# SAM3U_Test_Schematic.net
KiCad netlist of a schematic drawn in EAGLE
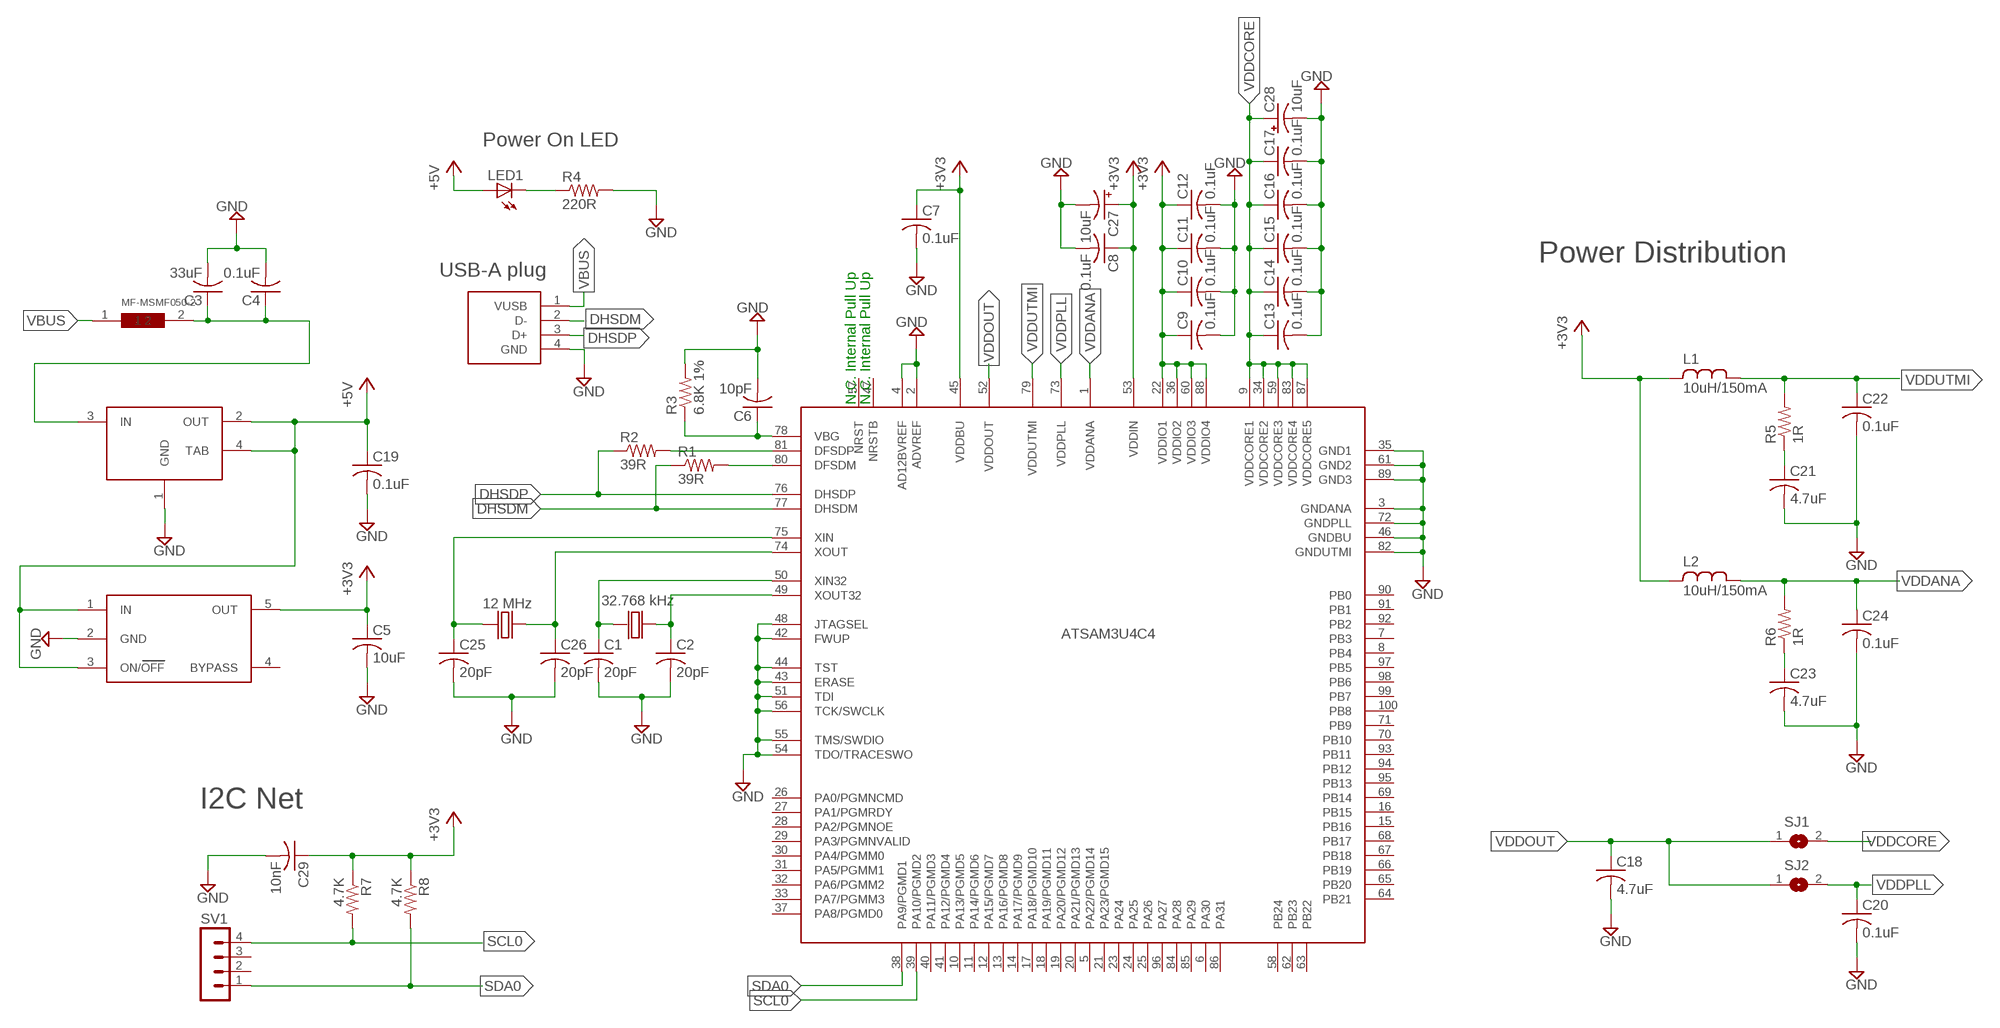
[diagram p0: schematic, sheet 1]

(export (version "E")
  (design (tool "Eeschema 10.0.6"))
  (components
    (comp (ref "C1")
      (value "20pF")
      (footprint "eagle-import:C0402K")
      (libsource (lib "eagle-import") (part "C-USC0402K"))
    )
    (comp (ref "C2")
      (value "20pF")
      (footprint "eagle-import:C0402K")
      (libsource (lib "eagle-import") (part "C-USC0402K"))
    )
    (comp (ref "C3")
      (value "33uF")
      (footprint "eagle-import:C0805K")
      (libsource (lib "eagle-import") (part "C-USC0805K"))
    )
    (comp (ref "C4")
      (value "0.1uF")
      (footprint "eagle-import:C0402K")
      (libsource (lib "eagle-import") (part "C-USC0402K"))
    )
    (comp (ref "C5")
      (value "10uF")
      (footprint "eagle-import:C0402K")
      (libsource (lib "eagle-import") (part "C-USC0402K"))
    )
    (comp (ref "C6")
      (value "10pF")
      (footprint "eagle-import:C0402K")
      (libsource (lib "eagle-import") (part "C-USC0402K"))
    )
    (comp (ref "C7")
      (value "0.1uF")
      (footprint "eagle-import:C0402K")
      (libsource (lib "eagle-import") (part "C-USC0402K"))
    )
    (comp (ref "C8")
      (value "0.1uF")
      (footprint "eagle-import:C0402K")
      (libsource (lib "eagle-import") (part "C-USC0402K"))
    )
    (comp (ref "C9")
      (value "0.1uF")
      (footprint "eagle-import:C0402K")
      (libsource (lib "eagle-import") (part "C-USC0402K"))
    )
    (comp (ref "C10")
      (value "0.1uF")
      (footprint "eagle-import:C0402K")
      (libsource (lib "eagle-import") (part "C-USC0402K"))
    )
    (comp (ref "C11")
      (value "0.1uF")
      (footprint "eagle-import:C0402K")
      (libsource (lib "eagle-import") (part "C-USC0402K"))
    )
    (comp (ref "C12")
      (value "0.1uF")
      (footprint "eagle-import:C0402K")
      (libsource (lib "eagle-import") (part "C-USC0402K"))
    )
    (comp (ref "C13")
      (value "0.1uF")
      (footprint "eagle-import:C0402K")
      (libsource (lib "eagle-import") (part "C-USC0402K"))
    )
    (comp (ref "C14")
      (value "0.1uF")
      (footprint "eagle-import:C0402K")
      (libsource (lib "eagle-import") (part "C-USC0402K"))
    )
    (comp (ref "C15")
      (value "0.1uF")
      (footprint "eagle-import:C0402K")
      (libsource (lib "eagle-import") (part "C-USC0402K"))
    )
    (comp (ref "C16")
      (value "0.1uF")
      (footprint "eagle-import:C0402K")
      (libsource (lib "eagle-import") (part "C-USC0402K"))
    )
    (comp (ref "C17")
      (value "0.1uF")
      (footprint "eagle-import:C0402K")
      (libsource (lib "eagle-import") (part "C-USC0402K"))
    )
    (comp (ref "C18")
      (value "4.7uF")
      (footprint "eagle-import:C0402K")
      (libsource (lib "eagle-import") (part "C-USC0402K"))
    )
    (comp (ref "C19")
      (value "0.1uF")
      (footprint "eagle-import:C0402K")
      (libsource (lib "eagle-import") (part "C-USC0402K"))
    )
    (comp (ref "C20")
      (value "0.1uF")
      (footprint "eagle-import:C0402K")
      (libsource (lib "eagle-import") (part "C-USC0402K"))
    )
    (comp (ref "C21")
      (value "4.7uF")
      (footprint "eagle-import:C0402K")
      (libsource (lib "eagle-import") (part "C-USC0402K"))
    )
    (comp (ref "C22")
      (value "0.1uF")
      (footprint "eagle-import:C0402K")
      (libsource (lib "eagle-import") (part "C-USC0402K"))
    )
    (comp (ref "C23")
      (value "4.7uF")
      (footprint "eagle-import:C0402K")
      (libsource (lib "eagle-import") (part "C-USC0402K"))
    )
    (comp (ref "C24")
      (value "0.1uF")
      (footprint "eagle-import:C0402K")
      (libsource (lib "eagle-import") (part "C-USC0402K"))
    )
    (comp (ref "C25")
      (value "20pF")
      (footprint "eagle-import:C0402K")
      (libsource (lib "eagle-import") (part "C-USC0402K"))
    )
    (comp (ref "C26")
      (value "20pF")
      (footprint "eagle-import:C0402K")
      (libsource (lib "eagle-import") (part "C-USC0402K"))
    )
    (comp (ref "C27")
      (value "10uF")
      (footprint "eagle-import:A_3216-18R")
      (libsource (lib "eagle-import") (part "CPOL-USA/3216-18R"))
    )
    (comp (ref "C28")
      (value "10uF")
      (footprint "eagle-import:A_3216-18R")
      (libsource (lib "eagle-import") (part "CPOL-USA/3216-18R"))
    )
    (comp (ref "C29")
      (value "10nF")
      (footprint "eagle-import:C0402K")
      (libsource (lib "eagle-import") (part "C-USC0402K"))
    )
    (comp (ref "L1")
      (value "TDK_MLZ2012_INDUCTOR")
      (footprint "eagle-import:TDK_MLZ_INDUCTOR_2012PACK")
      (libsource (lib "eagle-import") (part "TDK_MLZ2012_INDUCTOR"))
    )
    (comp (ref "L2")
      (value "TDK_MLZ2012_INDUCTOR")
      (footprint "eagle-import:TDK_MLZ_INDUCTOR_2012PACK")
      (libsource (lib "eagle-import") (part "TDK_MLZ2012_INDUCTOR"))
    )
    (comp (ref "LED1")
      (value "LEDCHIPLED_0603")
      (footprint "eagle-import:CHIPLED_0603")
      (libsource (lib "eagle-import") (part "LEDCHIPLED_0603"))
    )
    (comp (ref "R1")
      (value "39R")
      (footprint "eagle-import:R0402")
      (libsource (lib "eagle-import") (part "R-US_R0402"))
    )
    (comp (ref "R2")
      (value "39R")
      (footprint "eagle-import:R0402")
      (libsource (lib "eagle-import") (part "R-US_R0402"))
    )
    (comp (ref "R3")
      (value "6.8K 1%")
      (footprint "eagle-import:R0402")
      (libsource (lib "eagle-import") (part "R-US_R0402"))
    )
    (comp (ref "R4")
      (value "220R")
      (footprint "eagle-import:R0402")
      (libsource (lib "eagle-import") (part "R-US_R0402"))
    )
    (comp (ref "R5")
      (value "1R")
      (footprint "eagle-import:R0402")
      (libsource (lib "eagle-import") (part "R-US_R0402"))
    )
    (comp (ref "R6")
      (value "1R")
      (footprint "eagle-import:R0402")
      (libsource (lib "eagle-import") (part "R-US_R0402"))
    )
    (comp (ref "R7")
      (value "4.7K")
      (footprint "eagle-import:R0402")
      (libsource (lib "eagle-import") (part "R-US_R0402"))
    )
    (comp (ref "R8")
      (value "4.7K")
      (footprint "eagle-import:R0402")
      (libsource (lib "eagle-import") (part "R-US_R0402"))
    )
    (comp (ref "SJ1") (value "SJ") (footprint "eagle-import:SJ") (libsource (lib "eagle-import") (part "SJ")))
    (comp (ref "SJ2") (value "SJ") (footprint "eagle-import:SJ") (libsource (lib "eagle-import") (part "SJ")))
    (comp (ref "SV1")
      (value "MA04-1")
      (footprint "eagle-import:MA04-1")
      (libsource (lib "eagle-import") (part "MA04-1"))
    )
    (comp (ref "U$1")
      (value "USB_TYPE_A_KEYSTN")
      (footprint "eagle-import:USB_TYPE_PLUG_KSTN_PACK")
      (libsource (lib "eagle-import") (part "USB_TYPE_A_KEYSTN"))
    )
    (comp (ref "U$2")
      (value "ATSAM3UC4-PA")
      (footprint "eagle-import:QFP50P1600X1600X160-100N")
      (libsource (lib "eagle-import") (part "ATSAM3UC4-PA"))
    )
    (comp (ref "U$3")
      (value "32678_KYOCERA")
      (footprint "eagle-import:32678_KYOCERA_PACK")
      (libsource (lib "eagle-import") (part "32678_KYOCERA"))
    )
    (comp (ref "U$4")
      (value "MF-MSMF050-2")
      (footprint "eagle-import:MF-MSMF050-PACK")
      (libsource (lib "eagle-import") (part "MF-MSMF050-2"))
    )
    (comp (ref "U$5")
      (value "NCP1117-55V")
      (footprint "eagle-import:NCP1117-5-SOT")
      (libsource (lib "eagle-import") (part "NCP1117-55V"))
    )
    (comp (ref "U$6")
      (value "LP2985-33DBVR5-PIN")
      (footprint "eagle-import:LP2985-33DBVR-SO")
      (libsource (lib "eagle-import") (part "LP2985-33DBVR5-PIN"))
    )
    (comp (ref "U$7")
      (value "AVX_12MHZ_CRYSTAL_CX3225GB")
      (footprint "eagle-import:AVX_12MHZ_CX3225GB_PACK")
      (libsource (lib "eagle-import") (part "AVX_12MHZ_CRYSTAL_CX3225GB"))
    )
  )
  (nets
    (net (code "1") (name "+3V3") (class "Default")
      (node (ref "C10") (pin "1") (pinfunction "1_1") (pintype "passive"))
      (node (ref "C11") (pin "1") (pinfunction "1_1") (pintype "passive"))
      (node (ref "C12") (pin "1") (pinfunction "1_1") (pintype "passive"))
      (node (ref "C27") (pin "+") (pinfunction "+_+") (pintype "passive"))
      (node (ref "C29") (pin "1") (pinfunction "1_1") (pintype "passive"))
      (node (ref "C5") (pin "1") (pinfunction "1_1") (pintype "passive"))
      (node (ref "C7") (pin "1") (pinfunction "1_1") (pintype "passive"))
      (node (ref "C8") (pin "1") (pinfunction "1_1") (pintype "passive"))
      (node (ref "C9") (pin "1") (pinfunction "1_1") (pintype "passive"))
      (node (ref "L1") (pin "1") (pinfunction "P$1_1") (pintype "bidirectional"))
      (node (ref "L2") (pin "1") (pinfunction "P$1_1") (pintype "bidirectional"))
      (node (ref "R7") (pin "1") (pinfunction "1_1") (pintype "passive"))
      (node (ref "R8") (pin "1") (pinfunction "1_1") (pintype "passive"))
      (node (ref "U$2") (pin "22") (pinfunction "VDDIO1_22") (pintype "bidirectional"))
      (node (ref "U$2") (pin "36") (pinfunction "VDDIO2_36") (pintype "bidirectional"))
      (node (ref "U$2") (pin "45") (pinfunction "VDDBU_45") (pintype "bidirectional"))
      (node (ref "U$2") (pin "53") (pinfunction "VDDIN_53") (pintype "bidirectional"))
      (node (ref "U$2") (pin "60") (pinfunction "VDDIO3_60") (pintype "bidirectional"))
      (node (ref "U$2") (pin "88") (pinfunction "VDDIO4_88") (pintype "bidirectional"))
      (node (ref "U$6") (pin "5") (pinfunction "OUT_5") (pintype "bidirectional"))
    )
    (net (code "2") (name "+5V") (class "Default")
      (node (ref "C19") (pin "1") (pinfunction "1_1") (pintype "passive"))
      (node (ref "LED1") (pin "A") (pinfunction "A_A") (pintype "passive"))
      (node (ref "U$5") (pin "2") (pinfunction "OUT_2") (pintype "bidirectional"))
      (node (ref "U$5") (pin "4") (pinfunction "TAB_4") (pintype "bidirectional"))
      (node (ref "U$6") (pin "1") (pinfunction "IN_1") (pintype "bidirectional"))
      (node (ref "U$6") (pin "3") (pinfunction "ON/OFF_3") (pintype "bidirectional"))
    )
    (net (code "3") (name "DHSDM") (class "Default")
      (node (ref "R1") (pin "1") (pinfunction "1_1") (pintype "passive"))
      (node (ref "U$1") (pin "2") (pinfunction "D-_2") (pintype "bidirectional"))
      (node (ref "U$2") (pin "77") (pinfunction "DHSDM_77") (pintype "bidirectional"))
    )
    (net (code "4") (name "DHSDP") (class "Default")
      (node (ref "R2") (pin "1") (pinfunction "1_1") (pintype "passive"))
      (node (ref "U$1") (pin "3") (pinfunction "D+_3") (pintype "bidirectional"))
      (node (ref "U$2") (pin "76") (pinfunction "DHSDP_76") (pintype "bidirectional"))
    )
    (net (code "5") (name "GND") (class "Default")
      (node (ref "C1") (pin "2") (pinfunction "2_2") (pintype "passive"))
      (node (ref "C10") (pin "2") (pinfunction "2_2") (pintype "passive"))
      (node (ref "C11") (pin "2") (pinfunction "2_2") (pintype "passive"))
      (node (ref "C12") (pin "2") (pinfunction "2_2") (pintype "passive"))
      (node (ref "C13") (pin "2") (pinfunction "2_2") (pintype "passive"))
      (node (ref "C14") (pin "2") (pinfunction "2_2") (pintype "passive"))
      (node (ref "C15") (pin "2") (pinfunction "2_2") (pintype "passive"))
      (node (ref "C16") (pin "2") (pinfunction "2_2") (pintype "passive"))
      (node (ref "C17") (pin "2") (pinfunction "2_2") (pintype "passive"))
      (node (ref "C18") (pin "2") (pinfunction "2_2") (pintype "passive"))
      (node (ref "C19") (pin "2") (pinfunction "2_2") (pintype "passive"))
      (node (ref "C2") (pin "2") (pinfunction "2_2") (pintype "passive"))
      (node (ref "C20") (pin "2") (pinfunction "2_2") (pintype "passive"))
      (node (ref "C21") (pin "2") (pinfunction "2_2") (pintype "passive"))
      (node (ref "C22") (pin "2") (pinfunction "2_2") (pintype "passive"))
      (node (ref "C23") (pin "2") (pinfunction "2_2") (pintype "passive"))
      (node (ref "C24") (pin "2") (pinfunction "2_2") (pintype "passive"))
      (node (ref "C25") (pin "2") (pinfunction "2_2") (pintype "passive"))
      (node (ref "C26") (pin "2") (pinfunction "2_2") (pintype "passive"))
      (node (ref "C27") (pin "-") (pinfunction "-_-") (pintype "passive"))
      (node (ref "C28") (pin "-") (pinfunction "-_-") (pintype "passive"))
      (node (ref "C29") (pin "2") (pinfunction "2_2") (pintype "passive"))
      (node (ref "C3") (pin "2") (pinfunction "2_2") (pintype "passive"))
      (node (ref "C4") (pin "2") (pinfunction "2_2") (pintype "passive"))
      (node (ref "C5") (pin "2") (pinfunction "2_2") (pintype "passive"))
      (node (ref "C6") (pin "2") (pinfunction "2_2") (pintype "passive"))
      (node (ref "C7") (pin "2") (pinfunction "2_2") (pintype "passive"))
      (node (ref "C8") (pin "2") (pinfunction "2_2") (pintype "passive"))
      (node (ref "C9") (pin "2") (pinfunction "2_2") (pintype "passive"))
      (node (ref "R3") (pin "2") (pinfunction "2_2") (pintype "passive"))
      (node (ref "R4") (pin "2") (pinfunction "2_2") (pintype "passive"))
      (node (ref "U$1") (pin "4") (pinfunction "GND_4") (pintype "bidirectional"))
      (node (ref "U$2") (pin "2") (pinfunction "ADVREF_2") (pintype "bidirectional"))
      (node (ref "U$2") (pin "3") (pinfunction "GNDANA_3") (pintype "bidirectional"))
      (node (ref "U$2") (pin "35") (pinfunction "GND1_35") (pintype "bidirectional"))
      (node (ref "U$2") (pin "4") (pinfunction "AD12BVREF_4") (pintype "bidirectional"))
      (node (ref "U$2") (pin "42") (pinfunction "FWUP_42") (pintype "bidirectional"))
      (node (ref "U$2") (pin "43") (pinfunction "ERASE_43") (pintype "bidirectional"))
      (node (ref "U$2") (pin "44") (pinfunction "TST_44") (pintype "bidirectional"))
      (node (ref "U$2") (pin "46") (pinfunction "GNDBU_46") (pintype "bidirectional"))
      (node (ref "U$2") (pin "48") (pinfunction "JTAGSEL_48") (pintype "bidirectional"))
      (node (ref "U$2") (pin "51") (pinfunction "TDI_51") (pintype "bidirectional"))
      (node (ref "U$2") (pin "54") (pinfunction "TDO/TRACESWO_54") (pintype "bidirectional"))
      (node (ref "U$2") (pin "55") (pinfunction "TMS/SWDIO_55") (pintype "bidirectional"))
      (node (ref "U$2") (pin "56") (pinfunction "TCK/SWCLK_56") (pintype "bidirectional"))
      (node (ref "U$2") (pin "61") (pinfunction "GND2_61") (pintype "bidirectional"))
      (node (ref "U$2") (pin "72") (pinfunction "GNDPLL_72") (pintype "bidirectional"))
      (node (ref "U$2") (pin "82") (pinfunction "GNDUTMI_82") (pintype "bidirectional"))
      (node (ref "U$2") (pin "89") (pinfunction "GND3_89") (pintype "bidirectional"))
      (node (ref "U$5") (pin "1") (pinfunction "GND_1") (pintype "bidirectional"))
      (node (ref "U$6") (pin "2") (pinfunction "GND_2") (pintype "bidirectional"))
    )
    (net (code "6") (name "Net-(C21-Pad1)") (class "Default")
      (node (ref "C21") (pin "1") (pinfunction "1_1") (pintype "passive"))
      (node (ref "R5") (pin "1") (pinfunction "1_1") (pintype "passive"))
    )
    (net (code "7") (name "Net-(C23-Pad1)") (class "Default")
      (node (ref "C23") (pin "1") (pinfunction "1_1") (pintype "passive"))
      (node (ref "R6") (pin "1") (pinfunction "1_1") (pintype "passive"))
    )
    (net (code "8") (name "Net-(LED1-PadC)") (class "Default")
      (node (ref "LED1") (pin "C") (pinfunction "C_C") (pintype "passive"))
      (node (ref "R4") (pin "1") (pinfunction "1_1") (pintype "passive"))
    )
    (net (code "9") (name "Net-(U$2-DFSDM)") (class "Default")
      (node (ref "R1") (pin "2") (pinfunction "2_2") (pintype "passive"))
      (node (ref "U$2") (pin "80") (pinfunction "DFSDM_80") (pintype "bidirectional"))
    )
    (net (code "10") (name "Net-(U$2-DFSDP)") (class "Default")
      (node (ref "R2") (pin "2") (pinfunction "2_2") (pintype "passive"))
      (node (ref "U$2") (pin "81") (pinfunction "DFSDP_81") (pintype "bidirectional"))
    )
    (net (code "11") (name "Net-(U$2-VBG)") (class "Default")
      (node (ref "C6") (pin "1") (pinfunction "1_1") (pintype "passive"))
      (node (ref "R3") (pin "1") (pinfunction "1_1") (pintype "passive"))
      (node (ref "U$2") (pin "78") (pinfunction "VBG_78") (pintype "bidirectional"))
    )
    (net (code "12") (name "Net-(U$2-XIN)") (class "Default")
      (node (ref "C25") (pin "1") (pinfunction "1_1") (pintype "passive"))
      (node (ref "U$2") (pin "75") (pinfunction "XIN_75") (pintype "bidirectional"))
      (node (ref "U$7") (pin "1") (pinfunction "P$1_1") (pintype "bidirectional"))
    )
    (net (code "13") (name "Net-(U$2-XIN32)") (class "Default")
      (node (ref "C1") (pin "1") (pinfunction "1_1") (pintype "passive"))
      (node (ref "U$2") (pin "50") (pinfunction "XIN32_50") (pintype "bidirectional"))
      (node (ref "U$3") (pin "1") (pinfunction "P$1_1") (pintype "bidirectional"))
    )
    (net (code "14") (name "Net-(U$2-XOUT)") (class "Default")
      (node (ref "C26") (pin "1") (pinfunction "1_1") (pintype "passive"))
      (node (ref "U$2") (pin "74") (pinfunction "XOUT_74") (pintype "bidirectional"))
      (node (ref "U$7") (pin "3") (pinfunction "P$2_3") (pintype "bidirectional"))
    )
    (net (code "15") (name "Net-(U$2-XOUT32)") (class "Default")
      (node (ref "C2") (pin "1") (pinfunction "1_1") (pintype "passive"))
      (node (ref "U$2") (pin "49") (pinfunction "XOUT32_49") (pintype "bidirectional"))
      (node (ref "U$3") (pin "2") (pinfunction "P$2_2") (pintype "bidirectional"))
    )
    (net (code "16") (name "Net-(U$5-IN)") (class "Default")
      (node (ref "C3") (pin "1") (pinfunction "1_1") (pintype "passive"))
      (node (ref "C4") (pin "1") (pinfunction "1_1") (pintype "passive"))
      (node (ref "U$4") (pin "2") (pinfunction "2_2") (pintype "bidirectional"))
      (node (ref "U$5") (pin "3") (pinfunction "IN_3") (pintype "bidirectional"))
    )
    (net (code "17") (name "SCL0") (class "Default")
      (node (ref "R7") (pin "2") (pinfunction "2_2") (pintype "passive"))
      (node (ref "SV1") (pin "4") (pinfunction "4_4") (pintype "passive"))
      (node (ref "U$2") (pin "39") (pinfunction "PA10/PGMD2_39") (pintype "bidirectional"))
    )
    (net (code "18") (name "SDA0") (class "Default")
      (node (ref "R8") (pin "2") (pinfunction "2_2") (pintype "passive"))
      (node (ref "SV1") (pin "1") (pinfunction "1_1") (pintype "passive"))
      (node (ref "U$2") (pin "38") (pinfunction "PA9/PGMD1_38") (pintype "bidirectional"))
    )
    (net (code "19") (name "VBUS") (class "Default")
      (node (ref "U$1") (pin "1") (pinfunction "VUSB_1") (pintype "bidirectional"))
      (node (ref "U$4") (pin "1") (pinfunction "1_1") (pintype "bidirectional"))
    )
    (net (code "20") (name "VDDANA") (class "Default")
      (node (ref "C24") (pin "1") (pinfunction "1_1") (pintype "passive"))
      (node (ref "L2") (pin "2") (pinfunction "P$2_2") (pintype "bidirectional"))
      (node (ref "R6") (pin "2") (pinfunction "2_2") (pintype "passive"))
      (node (ref "U$2") (pin "1") (pinfunction "VDDANA_1") (pintype "bidirectional"))
    )
    (net (code "21") (name "VDDCORE") (class "Default")
      (node (ref "C13") (pin "1") (pinfunction "1_1") (pintype "passive"))
      (node (ref "C14") (pin "1") (pinfunction "1_1") (pintype "passive"))
      (node (ref "C15") (pin "1") (pinfunction "1_1") (pintype "passive"))
      (node (ref "C16") (pin "1") (pinfunction "1_1") (pintype "passive"))
      (node (ref "C17") (pin "1") (pinfunction "1_1") (pintype "passive"))
      (node (ref "C28") (pin "+") (pinfunction "+_+") (pintype "passive"))
      (node (ref "SJ1") (pin "2") (pinfunction "2_2") (pintype "passive"))
      (node (ref "U$2") (pin "34") (pinfunction "VDDCORE2_34") (pintype "bidirectional"))
      (node (ref "U$2") (pin "59") (pinfunction "VDDCORE3_59") (pintype "bidirectional"))
      (node (ref "U$2") (pin "83") (pinfunction "VDDCORE4_83") (pintype "bidirectional"))
      (node (ref "U$2") (pin "87") (pinfunction "VDDCORE5_87") (pintype "bidirectional"))
      (node (ref "U$2") (pin "9") (pinfunction "VDDCORE1_9") (pintype "bidirectional"))
    )
    (net (code "22") (name "VDDOUT") (class "Default")
      (node (ref "C18") (pin "1") (pinfunction "1_1") (pintype "passive"))
      (node (ref "SJ1") (pin "1") (pinfunction "1_1") (pintype "passive"))
      (node (ref "SJ2") (pin "1") (pinfunction "1_1") (pintype "passive"))
      (node (ref "U$2") (pin "52") (pinfunction "VDDOUT_52") (pintype "bidirectional"))
    )
    (net (code "23") (name "VDDPLL") (class "Default")
      (node (ref "C20") (pin "1") (pinfunction "1_1") (pintype "passive"))
      (node (ref "SJ2") (pin "2") (pinfunction "2_2") (pintype "passive"))
      (node (ref "U$2") (pin "73") (pinfunction "VDDPLL_73") (pintype "bidirectional"))
    )
    (net (code "24") (name "VDDUTMI") (class "Default")
      (node (ref "C22") (pin "1") (pinfunction "1_1") (pintype "passive"))
      (node (ref "L1") (pin "2") (pinfunction "P$2_2") (pintype "bidirectional"))
      (node (ref "R5") (pin "2") (pinfunction "2_2") (pintype "passive"))
      (node (ref "U$2") (pin "79") (pinfunction "VDDUTMI_79") (pintype "bidirectional"))
    )
    (net (code "25") (name "unconnected-(SV1-Pad2)") (class "Default")
      (node (ref "SV1") (pin "2") (pinfunction "2_2") (pintype "passive"))
    )
    (net (code "26") (name "unconnected-(SV1-Pad3)") (class "Default")
      (node (ref "SV1") (pin "3") (pinfunction "3_3") (pintype "passive"))
    )
    (net (code "27") (name "unconnected-(U$2-NRST-Pad57)") (class "Default")
      (node (ref "U$2") (pin "57") (pinfunction "NRST_57") (pintype "bidirectional"))
    )
    (net (code "28") (name "unconnected-(U$2-NRSTB-Pad47)") (class "Default")
      (node (ref "U$2") (pin "47") (pinfunction "NRSTB_47") (pintype "bidirectional"))
    )
    (net (code "29") (name "unconnected-(U$2-PA0{slash}PGMNCMD-Pad26)") (class "Default")
      (node (ref "U$2") (pin "26") (pinfunction "PA0/PGMNCMD_26") (pintype "bidirectional"))
    )
    (net (code "30") (name "unconnected-(U$2-PA1{slash}PGMRDY-Pad27)") (class "Default")
      (node (ref "U$2") (pin "27") (pinfunction "PA1/PGMRDY_27") (pintype "bidirectional"))
    )
    (net (code "31") (name "unconnected-(U$2-PA2{slash}PGMNOE-Pad28)") (class "Default")
      (node (ref "U$2") (pin "28") (pinfunction "PA2/PGMNOE_28") (pintype "bidirectional"))
    )
    (net (code "32") (name "unconnected-(U$2-PA3{slash}PGMNVALID-Pad29)") (class "Default")
      (node (ref "U$2") (pin "29") (pinfunction "PA3/PGMNVALID_29") (pintype "bidirectional"))
    )
    (net (code "33") (name "unconnected-(U$2-PA4{slash}PGMM0-Pad30)") (class "Default")
      (node (ref "U$2") (pin "30") (pinfunction "PA4/PGMM0_30") (pintype "bidirectional"))
    )
    (net (code "34") (name "unconnected-(U$2-PA5{slash}PGMM1-Pad31)") (class "Default")
      (node (ref "U$2") (pin "31") (pinfunction "PA5/PGMM1_31") (pintype "bidirectional"))
    )
    (net (code "35") (name "unconnected-(U$2-PA6{slash}PGMM2-Pad32)") (class "Default")
      (node (ref "U$2") (pin "32") (pinfunction "PA6/PGMM2_32") (pintype "bidirectional"))
    )
    (net (code "36") (name "unconnected-(U$2-PA7{slash}PGMM3-Pad33)") (class "Default")
      (node (ref "U$2") (pin "33") (pinfunction "PA7/PGMM3_33") (pintype "bidirectional"))
    )
    (net (code "37") (name "unconnected-(U$2-PA8{slash}PGMD0-Pad37)") (class "Default")
      (node (ref "U$2") (pin "37") (pinfunction "PA8/PGMD0_37") (pintype "bidirectional"))
    )
    (net (code "38") (name "unconnected-(U$2-PA11{slash}PGMD3-Pad40)") (class "Default")
      (node (ref "U$2") (pin "40") (pinfunction "PA11/PGMD3_40") (pintype "bidirectional"))
    )
    (net (code "39") (name "unconnected-(U$2-PA12{slash}PGMD4-Pad41)") (class "Default")
      (node (ref "U$2") (pin "41") (pinfunction "PA12/PGMD4_41") (pintype "bidirectional"))
    )
    (net (code "40") (name "unconnected-(U$2-PA13{slash}PGMD5-Pad10)") (class "Default")
      (node (ref "U$2") (pin "10") (pinfunction "PA13/PGMD5_10") (pintype "bidirectional"))
    )
    (net (code "41") (name "unconnected-(U$2-PA14{slash}PGMD6-Pad11)") (class "Default")
      (node (ref "U$2") (pin "11") (pinfunction "PA14/PGMD6_11") (pintype "bidirectional"))
    )
    (net (code "42") (name "unconnected-(U$2-PA15{slash}PGMD7-Pad12)") (class "Default")
      (node (ref "U$2") (pin "12") (pinfunction "PA15/PGMD7_12") (pintype "bidirectional"))
    )
    (net (code "43") (name "unconnected-(U$2-PA16{slash}PGMD8-Pad13)") (class "Default")
      (node (ref "U$2") (pin "13") (pinfunction "PA16/PGMD8_13") (pintype "bidirectional"))
    )
    (net (code "44") (name "unconnected-(U$2-PA17{slash}PGMD9-Pad14)") (class "Default")
      (node (ref "U$2") (pin "14") (pinfunction "PA17/PGMD9_14") (pintype "bidirectional"))
    )
    (net (code "45") (name "unconnected-(U$2-PA18{slash}PGMD10-Pad17)") (class "Default")
      (node (ref "U$2") (pin "17") (pinfunction "PA18/PGMD10_17") (pintype "bidirectional"))
    )
    (net (code "46") (name "unconnected-(U$2-PA19{slash}PGMD11-Pad18)") (class "Default")
      (node (ref "U$2") (pin "18") (pinfunction "PA19/PGMD11_18") (pintype "bidirectional"))
    )
    (net (code "47") (name "unconnected-(U$2-PA20{slash}PGMD12-Pad19)") (class "Default")
      (node (ref "U$2") (pin "19") (pinfunction "PA20/PGMD12_19") (pintype "bidirectional"))
    )
    (net (code "48") (name "unconnected-(U$2-PA21{slash}PGMD13-Pad20)") (class "Default")
      (node (ref "U$2") (pin "20") (pinfunction "PA21/PGMD13_20") (pintype "bidirectional"))
    )
    (net (code "49") (name "unconnected-(U$2-PA22{slash}PGMD14-Pad5)") (class "Default")
      (node (ref "U$2") (pin "5") (pinfunction "PA22/PGMD14_5") (pintype "bidirectional"))
    )
    (net (code "50") (name "unconnected-(U$2-PA23{slash}PGMD15-Pad21)") (class "Default")
      (node (ref "U$2") (pin "21") (pinfunction "PA23/PGMD15_21") (pintype "bidirectional"))
    )
    (net (code "51") (name "unconnected-(U$2-PA24-Pad23)") (class "Default")
      (node (ref "U$2") (pin "23") (pinfunction "PA24_23") (pintype "bidirectional"))
    )
    (net (code "52") (name "unconnected-(U$2-PA25-Pad24)") (class "Default")
      (node (ref "U$2") (pin "24") (pinfunction "PA25_24") (pintype "bidirectional"))
    )
    (net (code "53") (name "unconnected-(U$2-PA26-Pad25)") (class "Default")
      (node (ref "U$2") (pin "25") (pinfunction "PA26_25") (pintype "bidirectional"))
    )
    (net (code "54") (name "unconnected-(U$2-PA27-Pad96)") (class "Default")
      (node (ref "U$2") (pin "96") (pinfunction "PA27_96") (pintype "bidirectional"))
    )
    (net (code "55") (name "unconnected-(U$2-PA28-Pad84)") (class "Default")
      (node (ref "U$2") (pin "84") (pinfunction "PA28_84") (pintype "bidirectional"))
    )
    (net (code "56") (name "unconnected-(U$2-PA29-Pad85)") (class "Default")
      (node (ref "U$2") (pin "85") (pinfunction "PA29_85") (pintype "bidirectional"))
    )
    (net (code "57") (name "unconnected-(U$2-PA30-Pad6)") (class "Default")
      (node (ref "U$2") (pin "6") (pinfunction "PA30_6") (pintype "bidirectional"))
    )
    (net (code "58") (name "unconnected-(U$2-PA31-Pad86)") (class "Default")
      (node (ref "U$2") (pin "86") (pinfunction "PA31_86") (pintype "bidirectional"))
    )
    (net (code "59") (name "unconnected-(U$2-PB0-Pad90)") (class "Default")
      (node (ref "U$2") (pin "90") (pinfunction "PB0_90") (pintype "bidirectional"))
    )
    (net (code "60") (name "unconnected-(U$2-PB1-Pad91)") (class "Default")
      (node (ref "U$2") (pin "91") (pinfunction "PB1_91") (pintype "bidirectional"))
    )
    (net (code "61") (name "unconnected-(U$2-PB2-Pad92)") (class "Default")
      (node (ref "U$2") (pin "92") (pinfunction "PB2_92") (pintype "bidirectional"))
    )
    (net (code "62") (name "unconnected-(U$2-PB3-Pad7)") (class "Default")
      (node (ref "U$2") (pin "7") (pinfunction "PB3_7") (pintype "bidirectional"))
    )
    (net (code "63") (name "unconnected-(U$2-PB4-Pad8)") (class "Default")
      (node (ref "U$2") (pin "8") (pinfunction "PB4_8") (pintype "bidirectional"))
    )
    (net (code "64") (name "unconnected-(U$2-PB5-Pad97)") (class "Default")
      (node (ref "U$2") (pin "97") (pinfunction "PB5_97") (pintype "bidirectional"))
    )
    (net (code "65") (name "unconnected-(U$2-PB6-Pad98)") (class "Default")
      (node (ref "U$2") (pin "98") (pinfunction "PB6_98") (pintype "bidirectional"))
    )
    (net (code "66") (name "unconnected-(U$2-PB7-Pad99)") (class "Default")
      (node (ref "U$2") (pin "99") (pinfunction "PB7_99") (pintype "bidirectional"))
    )
    (net (code "67") (name "unconnected-(U$2-PB8-Pad100)") (class "Default")
      (node (ref "U$2") (pin "100") (pinfunction "PB8_100") (pintype "bidirectional"))
    )
    (net (code "68") (name "unconnected-(U$2-PB9-Pad71)") (class "Default")
      (node (ref "U$2") (pin "71") (pinfunction "PB9_71") (pintype "bidirectional"))
    )
    (net (code "69") (name "unconnected-(U$2-PB10-Pad70)") (class "Default")
      (node (ref "U$2") (pin "70") (pinfunction "PB10_70") (pintype "bidirectional"))
    )
    (net (code "70") (name "unconnected-(U$2-PB11-Pad93)") (class "Default")
      (node (ref "U$2") (pin "93") (pinfunction "PB11_93") (pintype "bidirectional"))
    )
    (net (code "71") (name "unconnected-(U$2-PB12-Pad94)") (class "Default")
      (node (ref "U$2") (pin "94") (pinfunction "PB12_94") (pintype "bidirectional"))
    )
    (net (code "72") (name "unconnected-(U$2-PB13-Pad95)") (class "Default")
      (node (ref "U$2") (pin "95") (pinfunction "PB13_95") (pintype "bidirectional"))
    )
    (net (code "73") (name "unconnected-(U$2-PB14-Pad69)") (class "Default")
      (node (ref "U$2") (pin "69") (pinfunction "PB14_69") (pintype "bidirectional"))
    )
    (net (code "74") (name "unconnected-(U$2-PB15-Pad16)") (class "Default")
      (node (ref "U$2") (pin "16") (pinfunction "PB15_16") (pintype "bidirectional"))
    )
    (net (code "75") (name "unconnected-(U$2-PB16-Pad15)") (class "Default")
      (node (ref "U$2") (pin "15") (pinfunction "PB16_15") (pintype "bidirectional"))
    )
    (net (code "76") (name "unconnected-(U$2-PB17-Pad68)") (class "Default")
      (node (ref "U$2") (pin "68") (pinfunction "PB17_68") (pintype "bidirectional"))
    )
    (net (code "77") (name "unconnected-(U$2-PB18-Pad67)") (class "Default")
      (node (ref "U$2") (pin "67") (pinfunction "PB18_67") (pintype "bidirectional"))
    )
    (net (code "78") (name "unconnected-(U$2-PB19-Pad66)") (class "Default")
      (node (ref "U$2") (pin "66") (pinfunction "PB19_66") (pintype "bidirectional"))
    )
    (net (code "79") (name "unconnected-(U$2-PB20-Pad65)") (class "Default")
      (node (ref "U$2") (pin "65") (pinfunction "PB20_65") (pintype "bidirectional"))
    )
    (net (code "80") (name "unconnected-(U$2-PB21-Pad64)") (class "Default")
      (node (ref "U$2") (pin "64") (pinfunction "PB21_64") (pintype "bidirectional"))
    )
    (net (code "81") (name "unconnected-(U$2-PB22-Pad63)") (class "Default")
      (node (ref "U$2") (pin "63") (pinfunction "PB22_63") (pintype "bidirectional"))
    )
    (net (code "82") (name "unconnected-(U$2-PB23-Pad62)") (class "Default")
      (node (ref "U$2") (pin "62") (pinfunction "PB23_62") (pintype "bidirectional"))
    )
    (net (code "83") (name "unconnected-(U$2-PB24-Pad58)") (class "Default")
      (node (ref "U$2") (pin "58") (pinfunction "PB24_58") (pintype "bidirectional"))
    )
    (net (code "84") (name "unconnected-(U$6-BYPASS-Pad4)") (class "Default")
      (node (ref "U$6") (pin "4") (pinfunction "BYPASS_4") (pintype "bidirectional"))
    )
  )
)
